# 25H_v2.net
KiCad netlist of a schematic drawn in Altium Designer
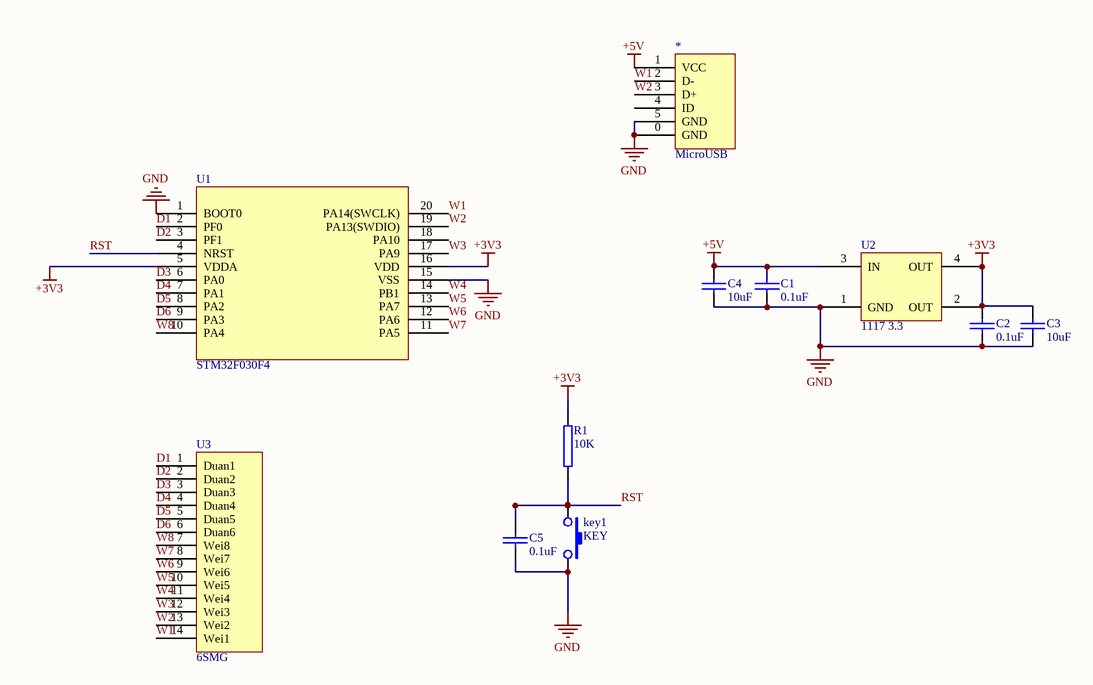
[diagram p0: 25H_v2.SchDoc]

(export (version "E")
  (design (tool "Eeschema 10.0.6"))
  (components
    (comp (ref "*") (value "MicroUSB") (footprint "MicroUSB") (libsource (lib "25H") (part "MicroUSB")))
    (comp (ref "C1") (value "0.1uF") (footprint "C0603") (libsource (lib "25H") (part "CAP")))
    (comp (ref "C2") (value "0.1uF") (footprint "C0603") (libsource (lib "25H") (part "CAP")))
    (comp (ref "C3") (value "10uF") (footprint "C0603") (libsource (lib "25H") (part "CAP")))
    (comp (ref "C4") (value "10uF") (footprint "C0603") (libsource (lib "25H") (part "CAP")))
    (comp (ref "C5") (value "0.1uF") (footprint "C0603") (libsource (lib "25H") (part "CAP")))
    (comp (ref "key1") (value "KEY") (footprint "KEY4*4*1.7") (libsource (lib "25H") (part "KEY")))
    (comp (ref "R1") (value "10K") (footprint "R0603") (libsource (lib "25H") (part "RES")))
    (comp (ref "U1")
      (value "STM32F030F4")
      (footprint "TSSOP-20")
      (libsource (lib "25H") (part "STM32F030F4"))
    )
    (comp (ref "U2") (value "1117 3.3") (footprint "SOT223") (libsource (lib "25H") (part "1117 3.3")))
    (comp (ref "U3") (value "6SMG") (footprint "6SMG") (libsource (lib "25H") (part "6SMG")))
  )
  (nets
    (net (code "1") (name "+3V3") (class "Default")
      (node (ref "C2") (pin "1") (pinfunction "1_1") (pintype "passive"))
      (node (ref "C3") (pin "1") (pinfunction "1_1") (pintype "passive"))
      (node (ref "R1") (pin "1") (pinfunction "1_1") (pintype "passive"))
      (node (ref "U1") (pin "16") (pinfunction "VDD_16") (pintype "passive"))
      (node (ref "U1") (pin "5") (pinfunction "VDDA_5") (pintype "passive"))
      (node (ref "U2") (pin "2") (pinfunction "OUT_2") (pintype "passive"))
      (node (ref "U2") (pin "4") (pinfunction "OUT_4") (pintype "passive"))
    )
    (net (code "2") (name "+5V") (class "Default")
      (node (ref "*") (pin "1") (pinfunction "VCC_1") (pintype "passive"))
      (node (ref "C1") (pin "1") (pinfunction "1_1") (pintype "passive"))
      (node (ref "C4") (pin "1") (pinfunction "1_1") (pintype "passive"))
      (node (ref "U2") (pin "3") (pinfunction "IN_3") (pintype "passive"))
    )
    (net (code "3") (name "/D1") (class "Default")
      (node (ref "U1") (pin "2") (pinfunction "PF0_2") (pintype "passive"))
      (node (ref "U3") (pin "1") (pinfunction "Duan1_1") (pintype "passive"))
    )
    (net (code "4") (name "/D2") (class "Default")
      (node (ref "U1") (pin "3") (pinfunction "PF1_3") (pintype "passive"))
      (node (ref "U3") (pin "2") (pinfunction "Duan2_2") (pintype "passive"))
    )
    (net (code "5") (name "/D3") (class "Default")
      (node (ref "U1") (pin "6") (pinfunction "PA0_6") (pintype "passive"))
      (node (ref "U3") (pin "3") (pinfunction "Duan3_3") (pintype "passive"))
    )
    (net (code "6") (name "/D4") (class "Default")
      (node (ref "U1") (pin "7") (pinfunction "PA1_7") (pintype "passive"))
      (node (ref "U3") (pin "4") (pinfunction "Duan4_4") (pintype "passive"))
    )
    (net (code "7") (name "/D5") (class "Default")
      (node (ref "U1") (pin "8") (pinfunction "PA2_8") (pintype "passive"))
      (node (ref "U3") (pin "5") (pinfunction "Duan5_5") (pintype "passive"))
    )
    (net (code "8") (name "/D6") (class "Default")
      (node (ref "U1") (pin "9") (pinfunction "PA3_9") (pintype "passive"))
      (node (ref "U3") (pin "6") (pinfunction "Duan6_6") (pintype "passive"))
    )
    (net (code "9") (name "/RST") (class "Default")
      (node (ref "C5") (pin "1") (pinfunction "1_1") (pintype "passive"))
      (node (ref "R1") (pin "2") (pinfunction "2_2") (pintype "passive"))
      (node (ref "U1") (pin "4") (pinfunction "NRST_4") (pintype "passive"))
      (node (ref "key1") (pin "1") (pinfunction "1_1") (pintype "passive"))
    )
    (net (code "10") (name "/W1") (class "Default")
      (node (ref "*") (pin "2") (pinfunction "D-_2") (pintype "passive"))
      (node (ref "U1") (pin "20") (pinfunction "PA14(SWCLK)_20") (pintype "passive"))
      (node (ref "U3") (pin "14") (pinfunction "Wei1_14") (pintype "passive"))
    )
    (net (code "11") (name "/W2") (class "Default")
      (node (ref "*") (pin "3") (pinfunction "D+_3") (pintype "passive"))
      (node (ref "U1") (pin "19") (pinfunction "PA13(SWDIO)_19") (pintype "passive"))
      (node (ref "U3") (pin "13") (pinfunction "Wei2_13") (pintype "passive"))
    )
    (net (code "12") (name "/W3") (class "Default")
      (node (ref "U1") (pin "17") (pinfunction "PA9_17") (pintype "passive"))
      (node (ref "U3") (pin "12") (pinfunction "Wei3_12") (pintype "passive"))
    )
    (net (code "13") (name "/W4") (class "Default")
      (node (ref "U1") (pin "14") (pinfunction "PB1_14") (pintype "passive"))
      (node (ref "U3") (pin "11") (pinfunction "Wei4_11") (pintype "passive"))
    )
    (net (code "14") (name "/W5") (class "Default")
      (node (ref "U1") (pin "13") (pinfunction "PA7_13") (pintype "passive"))
      (node (ref "U3") (pin "10") (pinfunction "Wei5_10") (pintype "passive"))
    )
    (net (code "15") (name "/W6") (class "Default")
      (node (ref "U1") (pin "12") (pinfunction "PA6_12") (pintype "passive"))
      (node (ref "U3") (pin "9") (pinfunction "Wei6_9") (pintype "passive"))
    )
    (net (code "16") (name "/W7") (class "Default")
      (node (ref "U1") (pin "11") (pinfunction "PA5_11") (pintype "passive"))
      (node (ref "U3") (pin "8") (pinfunction "Wei7_8") (pintype "passive"))
    )
    (net (code "17") (name "/W8") (class "Default")
      (node (ref "U1") (pin "10") (pinfunction "PA4_10") (pintype "passive"))
      (node (ref "U3") (pin "7") (pinfunction "Wei8_7") (pintype "passive"))
    )
    (net (code "18") (name "GND") (class "Default")
      (node (ref "*") (pin "0") (pinfunction "GND_0") (pintype "passive"))
      (node (ref "*") (pin "5") (pinfunction "GND_5") (pintype "passive"))
      (node (ref "C1") (pin "2") (pinfunction "2_2") (pintype "passive"))
      (node (ref "C2") (pin "2") (pinfunction "2_2") (pintype "passive"))
      (node (ref "C3") (pin "2") (pinfunction "2_2") (pintype "passive"))
      (node (ref "C4") (pin "2") (pinfunction "2_2") (pintype "passive"))
      (node (ref "C5") (pin "2") (pinfunction "2_2") (pintype "passive"))
      (node (ref "U1") (pin "1") (pinfunction "BOOT0_1") (pintype "passive"))
      (node (ref "U1") (pin "15") (pinfunction "VSS_15") (pintype "passive"))
      (node (ref "U2") (pin "1") (pinfunction "GND_1") (pintype "passive"))
      (node (ref "key1") (pin "2") (pinfunction "2_2") (pintype "passive"))
    )
    (net (code "19") (name "unconnected-(*-ID-Pad4)") (class "Default")
      (node (ref "*") (pin "4") (pinfunction "ID_4") (pintype "passive"))
    )
    (net (code "20") (name "unconnected-(U1-PA10-Pad18)") (class "Default")
      (node (ref "U1") (pin "18") (pinfunction "PA10_18") (pintype "passive"))
    )
  )
)
